# Board_Power.net
KiCad netlist of a schematic drawn in Altium Designer
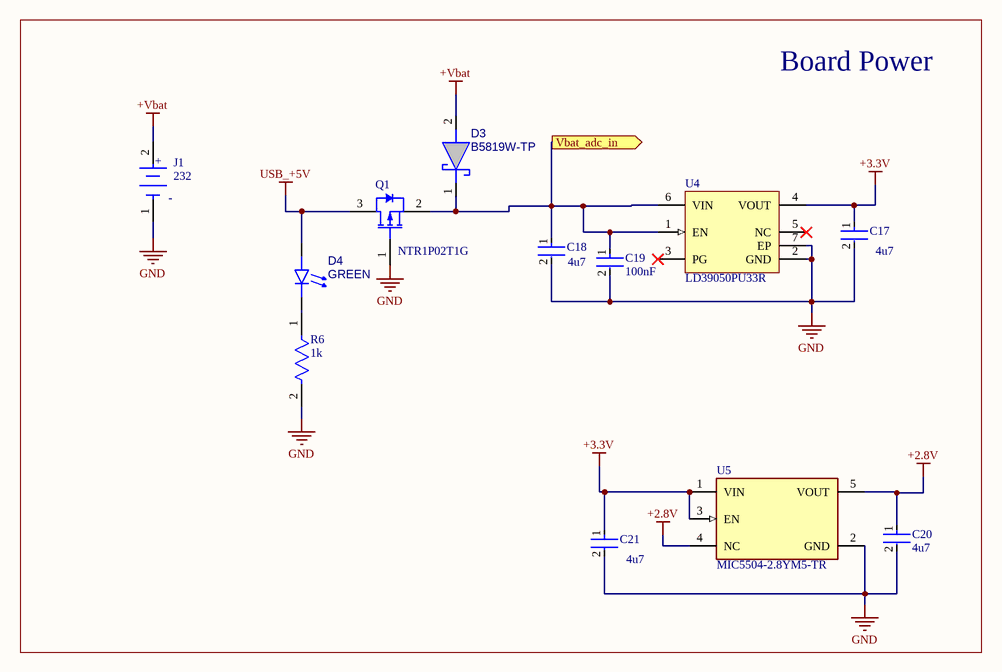
[diagram p0: Board_Power.SchDoc]

(export (version "E")
  (design (tool "Eeschema 10.0.6"))
  (components
    (comp (ref "C17")
      (value "4u7")
      (footprint "FP-GRM21B-0_15-MFG")
      (description "Chip Multilayer Ceramic Capacitors for General Purpose, 0805, 4.7uF, X7R, 15%, 10%, 10V")
      (fields (field (name "TOLERANCE") "10%"))
      (libsource (lib "Altium Content Vault") (part "b4654b650e69147ec39a6b967a45e02"))
    )
    (comp (ref "C18")
      (value "4u7")
      (footprint "FP-GRM21B-0_15-MFG")
      (description "Chip Multilayer Ceramic Capacitors for General Purpose, 0805, 4.7uF, X7R, 15%, 10%, 10V")
      (fields (field (name "TOLERANCE") "10%"))
      (libsource (lib "Altium Content Vault") (part "b4654b650e69147ec39a6b967a45e02"))
    )
    (comp (ref "C19")
      (value "100nF")
      (footprint "FP-C1206C-EB-MFG")
      (description "CAP CER 0.1UF 16V 10% X7R 1206")
      (fields (field (name "MANUFACTURER PART NUMBER") "C1206C104K4RACTU") (field (name "TOLERANCE") "0.1"))
      (libsource (lib "Altium Content Vault") (part "b4654b650e69147ec39a6b967a45e02"))
    )
    (comp (ref "C20")
      (value "4u7")
      (footprint "FP-GRM21B-0_15-MFG")
      (description "Chip Multilayer Ceramic Capacitors for General Purpose, 0805, 4.7uF, X7R, 15%, 10%, 10V")
      (fields (field (name "TOLERANCE") "10%"))
      (libsource (lib "Altium Content Vault") (part "b4654b650e69147ec39a6b967a45e02"))
    )
    (comp (ref "C21")
      (value "4u7")
      (footprint "FP-GRM21B-0_15-MFG")
      (description "Chip Multilayer Ceramic Capacitors for General Purpose, 0805, 4.7uF, X7R, 15%, 10%, 10V")
      (fields (field (name "TOLERANCE") "10%"))
      (libsource (lib "Altium Content Vault") (part "b4654b650e69147ec39a6b967a45e02"))
    )
    (comp (ref "D3")
      (value "B5819W-TP")
      (footprint "B5819W-TP-Footprint-1")
      (description "Rectifier Diode, Schottky, 1 Phase, 1 Element, 1A, 40V V(RRM), Silicon")
      (libsource (lib "tutorial_PCB") (part "B5819W-TP"))
    )
    (comp (ref "D4")
      (value "GREEN")
      (footprint "156120VS75000-Footprint-1")
      (description "Single Color LED")
      (libsource (lib "tutorial_PCB") (part "DIODE-LED-2"))
    )
    (comp (ref "J1")
      (value "232")
      (footprint "1043P-Footprint-1")
      (description "Batteries/Accessories")
      (libsource (lib "tutorial_PCB") (part "60d3b5b901a8747834971d0eb8cf3fd"))
    )
    (comp (ref "Q1")
      (value "NTR1P02T1G")
      (footprint "ONSC-SOT-23-3-318-08_V")
      (description "Power MOSFET, -20 V, -1 A, P-Channel, 3-Pin SOT-23, Pb-Free, Tape and Reel")
      (fields (field (name "MANUFACTURER") "On Semiconductor"))
      (libsource (lib "Altium Content Vault") (part "ONSC-PMOS-G1S2D3-3_D"))
    )
    (comp (ref "R6")
      (value "1k")
      (footprint "FP-RMCF1206-MFG")
      (description "1kΩ ±5% 0.25W 1206 Thick Film Chip Resistor AEC-Q200 compliant")
      (fields (field (name "TOLERANCE") "5%"))
      (libsource (lib "Altium Content Vault") (part "1029c3af85768c4190bb7ad29bc67b5"))
    )
    (comp (ref "U4")
      (value "LD39050PU33R")
      (footprint "DFN6D_L")
      (description "500 mA Low Quiescent Current Low Noise Voltage Regulator, 3.3V, 6-Pin VDFDPN, Tape and Reel")
      (libsource (lib "Altium Content Vault") (part "PM-REG-LD39050-SQ7"))
    )
    (comp (ref "U5")
      (value "MIC5504-2.8YM5-TR")
      (footprint "FP-SOT23-5LD-PL-1-IPC_C")
      (description "IC REG LINEAR 2.8V 300MA SOT23-5")
      (libsource (lib "Altium Content Vault") (part "49efecb8457b62bbb278fcbf558b656"))
    )
  )
  (nets
    (net (code "1") (name "+2.8V") (class "Default")
      (node (ref "C20") (pin "1") (pinfunction "1_1") (pintype "passive"))
      (node (ref "U5") (pin "4") (pinfunction "NC_4") (pintype "passive"))
      (node (ref "U5") (pin "5") (pinfunction "VOUT_5") (pintype "passive"))
    )
    (net (code "2") (name "+3.3V") (class "Default")
      (node (ref "C17") (pin "1") (pinfunction "1_1") (pintype "passive"))
      (node (ref "C21") (pin "1") (pinfunction "1_1") (pintype "passive"))
      (node (ref "U4") (pin "4") (pinfunction "VOUT_4") (pintype "power_in"))
      (node (ref "U5") (pin "1") (pinfunction "VIN_1") (pintype "power_in"))
      (node (ref "U5") (pin "3") (pinfunction "EN_3") (pintype "input"))
    )
    (net (code "3") (name "+Vbat") (class "Default")
      (node (ref "D3") (pin "2") (pinfunction "A_2") (pintype "passive"))
      (node (ref "J1") (pin "2") (pinfunction "A_2") (pintype "passive"))
    )
    (net (code "4") (name "/Vbat_adc_in") (class "Default")
      (node (ref "C18") (pin "1") (pinfunction "1_1") (pintype "passive"))
      (node (ref "C19") (pin "1") (pinfunction "1_1") (pintype "passive"))
      (node (ref "D3") (pin "1") (pinfunction "K_1") (pintype "passive"))
      (node (ref "Q1") (pin "2") (pinfunction "S_2") (pintype "passive"))
      (node (ref "U4") (pin "1") (pinfunction "EN_1") (pintype "input"))
      (node (ref "U4") (pin "6") (pinfunction "VIN_6") (pintype "power_in"))
    )
    (net (code "5") (name "GND") (class "Default")
      (node (ref "C17") (pin "2") (pinfunction "2_2") (pintype "passive"))
      (node (ref "C18") (pin "2") (pinfunction "2_2") (pintype "passive"))
      (node (ref "C19") (pin "2") (pinfunction "2_2") (pintype "passive"))
      (node (ref "C20") (pin "2") (pinfunction "2_2") (pintype "passive"))
      (node (ref "C21") (pin "2") (pinfunction "2_2") (pintype "passive"))
      (node (ref "J1") (pin "1") (pinfunction "C_1") (pintype "passive"))
      (node (ref "Q1") (pin "1") (pinfunction "G_1") (pintype "passive"))
      (node (ref "R6") (pin "2") (pinfunction "2_2") (pintype "passive"))
      (node (ref "U4") (pin "2") (pinfunction "GND_2") (pintype "power_in"))
      (node (ref "U4") (pin "7") (pinfunction "EP_7") (pintype "power_in"))
      (node (ref "U5") (pin "2") (pinfunction "GND_2") (pintype "power_in"))
    )
    (net (code "6") (name "Net-(D4-K)") (class "Default")
      (node (ref "D4") (pin "1") (pinfunction "K_1") (pintype "passive"))
      (node (ref "R6") (pin "1") (pinfunction "1_1") (pintype "passive"))
    )
    (net (code "7") (name "USB_+5V") (class "Default")
      (node (ref "D4") (pin "2") (pinfunction "A_2") (pintype "passive"))
      (node (ref "Q1") (pin "3") (pinfunction "D_3") (pintype "passive"))
    )
    (net (code "8") (name "unconnected-(U4-NC-Pad5)") (class "Default")
      (node (ref "U4") (pin "5") (pinfunction "NC_5") (pintype "passive+no_connect"))
    )
    (net (code "9") (name "unconnected-(U4-PG-Pad3)") (class "Default")
      (node (ref "U4") (pin "3") (pinfunction "PG_3") (pintype "open_collector+no_connect"))
    )
  )
)
